# 03_-_HV_Input.net
KiCad netlist of a schematic drawn in Altium Designer
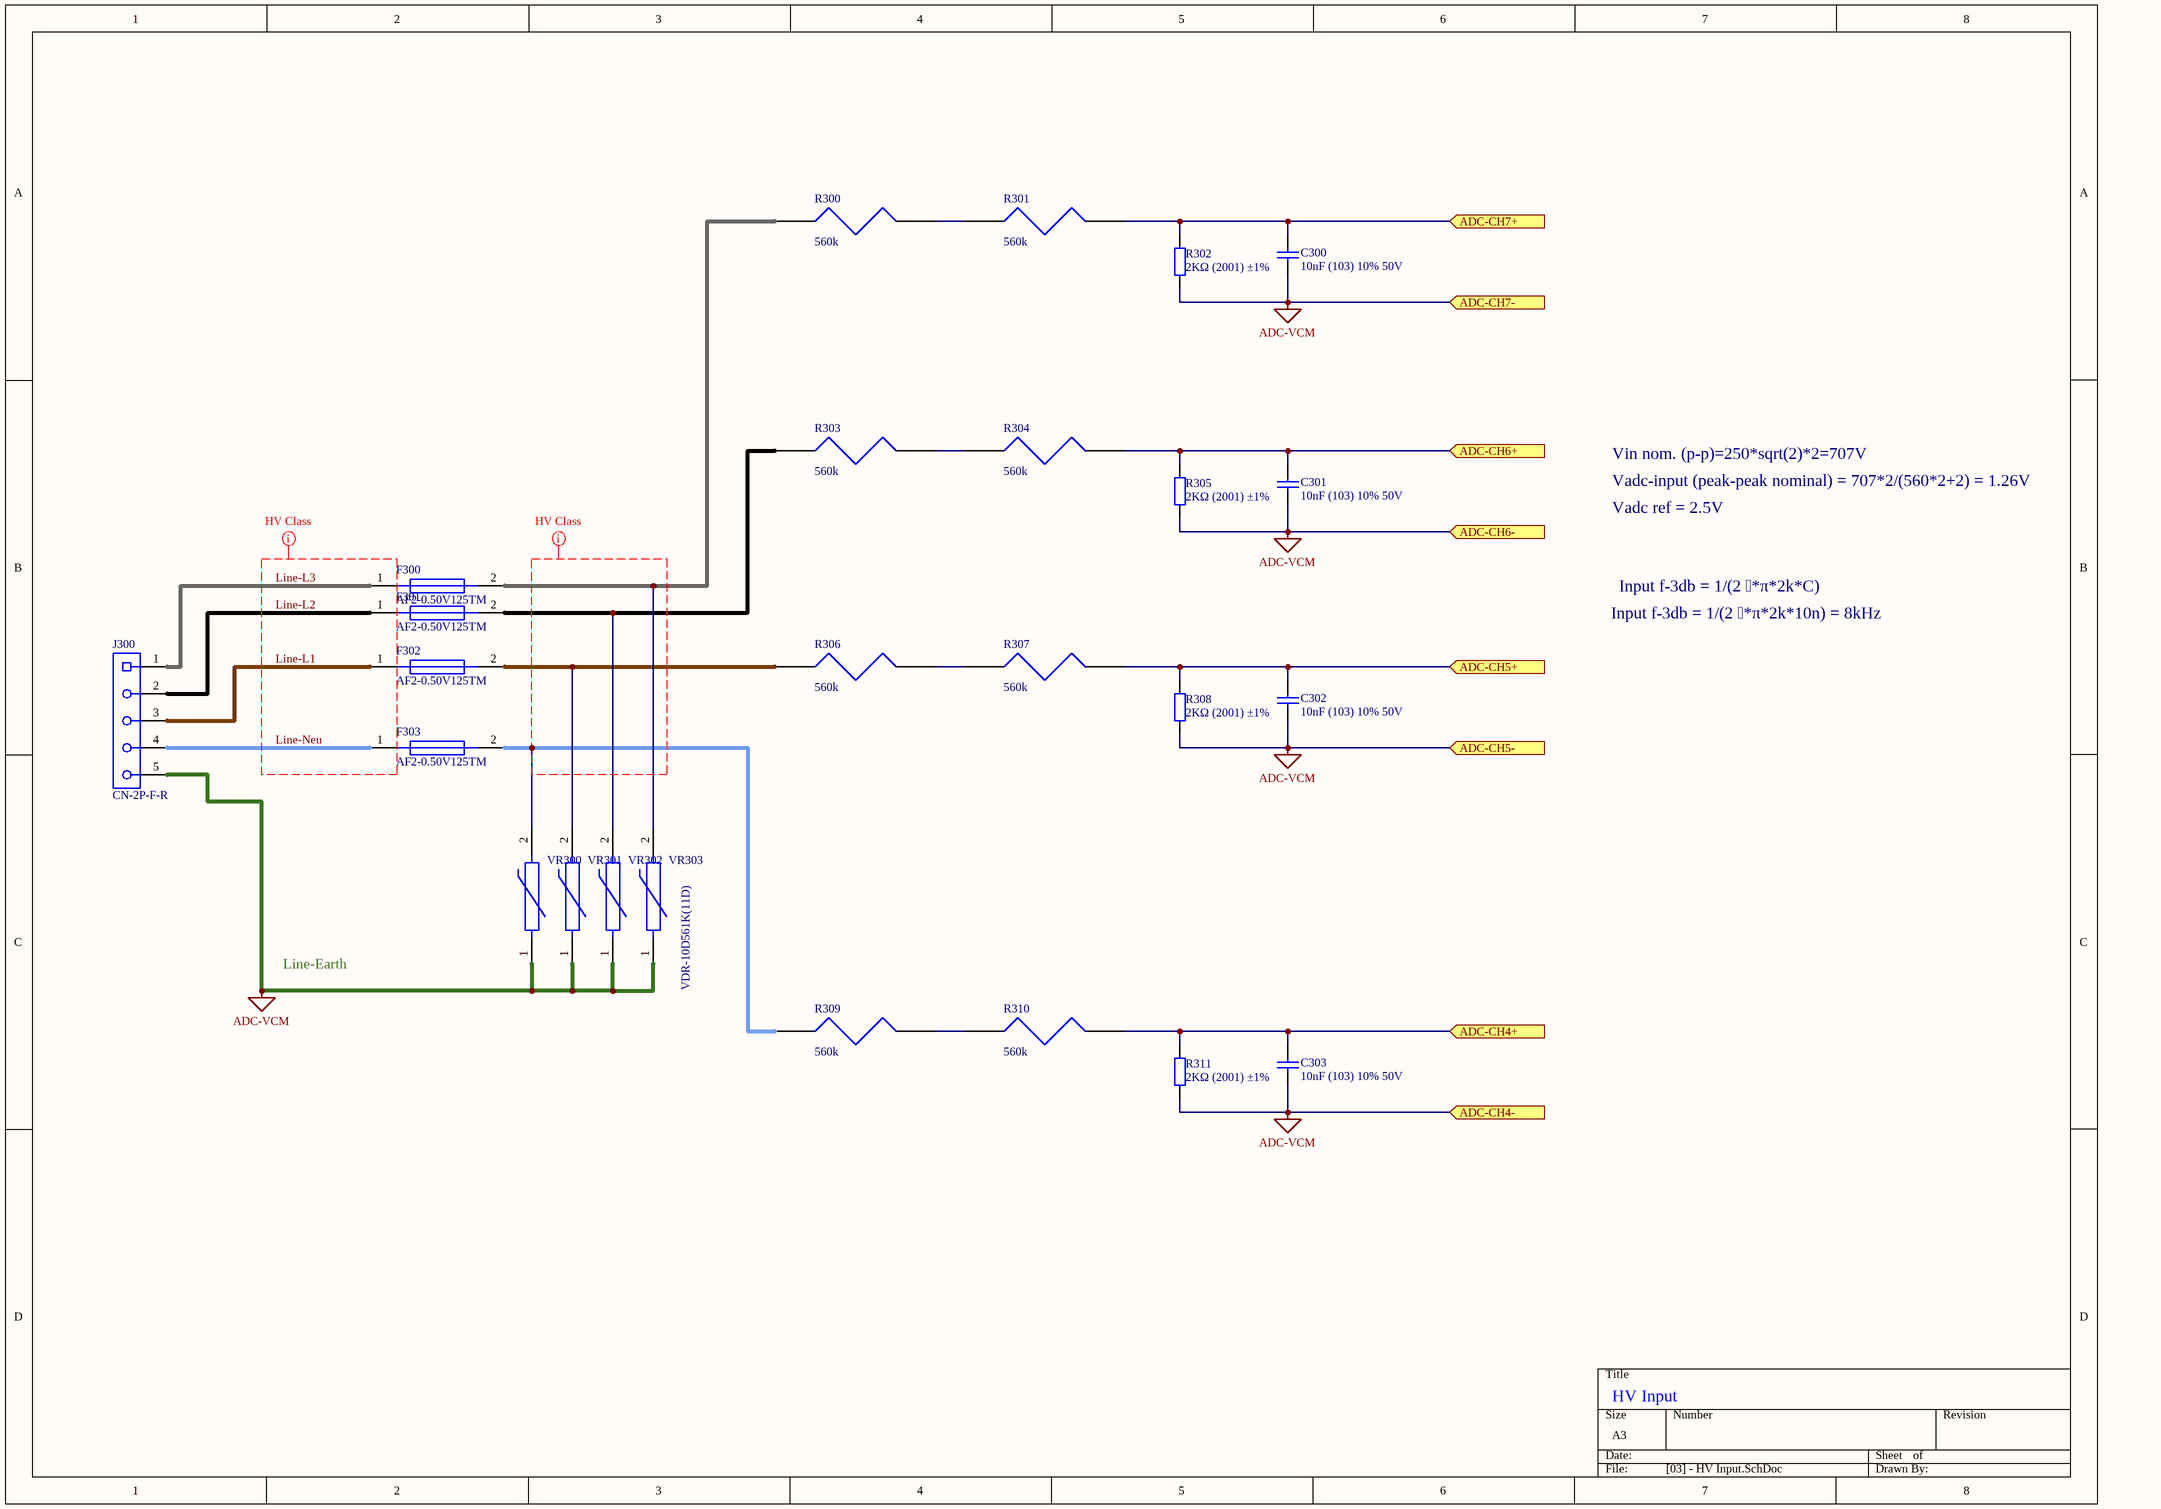
[diagram p0: [03] - HV Input.SchDoc]

(export (version "E")
  (design (tool "Eeschema 10.0.6"))
  (components
    (comp (ref "C300")
      (value "10nF (103) 10% 50V")
      (footprint "0805_C")
      (description "贴片电容")
      (libsource (lib "Cap") (part "0805 10nF (103) 10% 50V"))
    )
    (comp (ref "C301")
      (value "10nF (103) 10% 50V")
      (footprint "0805_C")
      (description "贴片电容")
      (libsource (lib "Cap") (part "0805 10nF (103) 10% 50V"))
    )
    (comp (ref "C302")
      (value "10nF (103) 10% 50V")
      (footprint "0805_C")
      (description "贴片电容")
      (libsource (lib "Cap") (part "0805 10nF (103) 10% 50V"))
    )
    (comp (ref "C303")
      (value "10nF (103) 10% 50V")
      (footprint "0805_C")
      (description "贴片电容")
      (libsource (lib "Cap") (part "0805 10nF (103) 10% 50V"))
    )
    (comp (ref "F300")
      (value "AF2-0.50V125TM")
      (footprint "2410 Fuse")
      (description "Chip Fuse Fast Blow 500mA 231mΩ 100A AC，50A DC 0.1 2410 Surface Mount Fuses RoHS")
      (libsource (lib "FPGA_PMU_lib") (part "AF2-0.50V125TM"))
    )
    (comp (ref "F301")
      (value "AF2-0.50V125TM")
      (footprint "2410 Fuse")
      (description "Chip Fuse Fast Blow 500mA 231mΩ 100A AC，50A DC 0.1 2410 Surface Mount Fuses RoHS")
      (libsource (lib "FPGA_PMU_lib") (part "AF2-0.50V125TM"))
    )
    (comp (ref "F302")
      (value "AF2-0.50V125TM")
      (footprint "2410 Fuse")
      (description "Chip Fuse Fast Blow 500mA 231mΩ 100A AC，50A DC 0.1 2410 Surface Mount Fuses RoHS")
      (libsource (lib "FPGA_PMU_lib") (part "AF2-0.50V125TM"))
    )
    (comp (ref "F303")
      (value "AF2-0.50V125TM")
      (footprint "2410 Fuse")
      (description "Chip Fuse Fast Blow 500mA 231mΩ 100A AC，50A DC 0.1 2410 Surface Mount Fuses RoHS")
      (libsource (lib "FPGA_PMU_lib") (part "AF2-0.50V125TM"))
    )
    (comp (ref "J300")
      (value "CN-2P-F-R")
      (footprint "PHOE-1729128-2_V")
      (description "5 Way - 10.16 block")
      (libsource (lib "xPMU_lib") (part "CN-2P-F-R"))
    )
    (comp (ref "R300")
      (value "560k")
      (footprint "FPGA_PMU_lib:2512_HV_RES")
      (description "HIGH VOLTAGE RESISTOR 560KOHMS ±1% 1W 2512 ROHS")
      (libsource (lib "FPGA_PMU_lib") (part "HR2512F560KE04Z"))
    )
    (comp (ref "R301")
      (value "560k")
      (footprint "FPGA_PMU_lib:2512_HV_RES")
      (description "HIGH VOLTAGE RESISTOR 560KOHMS ±1% 1W 2512 ROHS")
      (libsource (lib "FPGA_PMU_lib") (part "HR2512F560KE04Z"))
    )
    (comp (ref "R302")
      (value "2KΩ (2001) ±1%")
      (footprint "0805_R")
      (description "贴片电阻")
      (libsource (lib "RES") (part "0805 2KΩ (2001) 1%"))
    )
    (comp (ref "R303")
      (value "560k")
      (footprint "FPGA_PMU_lib:2512_HV_RES")
      (description "HIGH VOLTAGE RESISTOR 560KOHMS ±1% 1W 2512 ROHS")
      (libsource (lib "FPGA_PMU_lib") (part "HR2512F560KE04Z"))
    )
    (comp (ref "R304")
      (value "560k")
      (footprint "FPGA_PMU_lib:2512_HV_RES")
      (description "HIGH VOLTAGE RESISTOR 560KOHMS ±1% 1W 2512 ROHS")
      (libsource (lib "FPGA_PMU_lib") (part "HR2512F560KE04Z"))
    )
    (comp (ref "R305")
      (value "2KΩ (2001) ±1%")
      (footprint "0805_R")
      (description "贴片电阻")
      (libsource (lib "RES") (part "0805 2KΩ (2001) 1%"))
    )
    (comp (ref "R306")
      (value "560k")
      (footprint "FPGA_PMU_lib:2512_HV_RES")
      (description "HIGH VOLTAGE RESISTOR 560KOHMS ±1% 1W 2512 ROHS")
      (libsource (lib "FPGA_PMU_lib") (part "HR2512F560KE04Z"))
    )
    (comp (ref "R307")
      (value "560k")
      (footprint "FPGA_PMU_lib:2512_HV_RES")
      (description "HIGH VOLTAGE RESISTOR 560KOHMS ±1% 1W 2512 ROHS")
      (libsource (lib "FPGA_PMU_lib") (part "HR2512F560KE04Z"))
    )
    (comp (ref "R308")
      (value "2KΩ (2001) ±1%")
      (footprint "0805_R")
      (description "贴片电阻")
      (libsource (lib "RES") (part "0805 2KΩ (2001) 1%"))
    )
    (comp (ref "R309")
      (value "560k")
      (footprint "FPGA_PMU_lib:2512_HV_RES")
      (description "HIGH VOLTAGE RESISTOR 560KOHMS ±1% 1W 2512 ROHS")
      (libsource (lib "FPGA_PMU_lib") (part "HR2512F560KE04Z"))
    )
    (comp (ref "R310")
      (value "560k")
      (footprint "FPGA_PMU_lib:2512_HV_RES")
      (description "HIGH VOLTAGE RESISTOR 560KOHMS ±1% 1W 2512 ROHS")
      (libsource (lib "FPGA_PMU_lib") (part "HR2512F560KE04Z"))
    )
    (comp (ref "R311")
      (value "2KΩ (2001) ±1%")
      (footprint "0805_R")
      (description "贴片电阻")
      (libsource (lib "RES") (part "0805 2KΩ (2001) 1%"))
    )
    (comp (ref "VR300")
      (value "VDR-10D561K(11D)")
      (footprint "VDR-10D561K(11D)")
      (description "460V 920V 2.5KA 560V Through Hole Varistors RoHS")
      (libsource (lib "FPGA_PMU_lib") (part "VDR-10D561K(11D)"))
    )
    (comp (ref "VR301")
      (value "VDR-10D561K(11D)")
      (footprint "VDR-10D561K(11D)")
      (description "460V 920V 2.5KA 560V Through Hole Varistors RoHS")
      (libsource (lib "FPGA_PMU_lib") (part "VDR-10D561K(11D)"))
    )
    (comp (ref "VR302")
      (value "VDR-10D561K(11D)")
      (footprint "VDR-10D561K(11D)")
      (description "460V 920V 2.5KA 560V Through Hole Varistors RoHS")
      (libsource (lib "FPGA_PMU_lib") (part "VDR-10D561K(11D)"))
    )
    (comp (ref "VR303")
      (value "VDR-10D561K(11D)")
      (footprint "VDR-10D561K(11D)")
      (description "460V 920V 2.5KA 560V Through Hole Varistors RoHS")
      (libsource (lib "FPGA_PMU_lib") (part "VDR-10D561K(11D)"))
    )
  )
  (nets
    (net (code "1") (name "/ADC-CH4+") (class "Default")
      (node (ref "C303") (pin "2") (pinfunction "2_2") (pintype "passive"))
      (node (ref "R310") (pin "2") (pinfunction "2_2") (pintype "passive"))
      (node (ref "R311") (pin "2") (pinfunction "2_2") (pintype "passive"))
    )
    (net (code "2") (name "/ADC-CH5+") (class "Default")
      (node (ref "C302") (pin "2") (pinfunction "2_2") (pintype "passive"))
      (node (ref "R307") (pin "2") (pinfunction "2_2") (pintype "passive"))
      (node (ref "R308") (pin "2") (pinfunction "2_2") (pintype "passive"))
    )
    (net (code "3") (name "/ADC-CH6+") (class "Default")
      (node (ref "C301") (pin "2") (pinfunction "2_2") (pintype "passive"))
      (node (ref "R304") (pin "2") (pinfunction "2_2") (pintype "passive"))
      (node (ref "R305") (pin "2") (pinfunction "2_2") (pintype "passive"))
    )
    (net (code "4") (name "/ADC-CH7+") (class "Default")
      (node (ref "C300") (pin "2") (pinfunction "2_2") (pintype "passive"))
      (node (ref "R301") (pin "2") (pinfunction "2_2") (pintype "passive"))
      (node (ref "R302") (pin "2") (pinfunction "2_2") (pintype "passive"))
    )
    (net (code "5") (name "/Line-L1") (class "Default")
      (node (ref "F302") (pin "1") (pinfunction "1_1") (pintype "passive"))
      (node (ref "J300") (pin "3") (pinfunction "3_3") (pintype "passive"))
    )
    (net (code "6") (name "/Line-L2") (class "Default")
      (node (ref "F301") (pin "1") (pinfunction "1_1") (pintype "passive"))
      (node (ref "J300") (pin "2") (pinfunction "2_2") (pintype "passive"))
    )
    (net (code "7") (name "/Line-L3") (class "Default")
      (node (ref "F300") (pin "1") (pinfunction "1_1") (pintype "passive"))
      (node (ref "J300") (pin "1") (pinfunction "1_1") (pintype "passive"))
    )
    (net (code "8") (name "/Line-Neu") (class "Default")
      (node (ref "F303") (pin "1") (pinfunction "1_1") (pintype "passive"))
      (node (ref "J300") (pin "4") (pinfunction "4_4") (pintype "passive"))
    )
    (net (code "9") (name "ADC-VCM") (class "Default")
      (node (ref "C300") (pin "1") (pinfunction "1_1") (pintype "passive"))
      (node (ref "C301") (pin "1") (pinfunction "1_1") (pintype "passive"))
      (node (ref "C302") (pin "1") (pinfunction "1_1") (pintype "passive"))
      (node (ref "C303") (pin "1") (pinfunction "1_1") (pintype "passive"))
      (node (ref "J300") (pin "5") (pinfunction "5_5") (pintype "passive"))
      (node (ref "R302") (pin "1") (pinfunction "1_1") (pintype "passive"))
      (node (ref "R305") (pin "1") (pinfunction "1_1") (pintype "passive"))
      (node (ref "R308") (pin "1") (pinfunction "1_1") (pintype "passive"))
      (node (ref "R311") (pin "1") (pinfunction "1_1") (pintype "passive"))
      (node (ref "VR300") (pin "1") (pinfunction "1_1") (pintype "passive"))
      (node (ref "VR301") (pin "1") (pinfunction "1_1") (pintype "passive"))
      (node (ref "VR302") (pin "1") (pinfunction "1_1") (pintype "passive"))
      (node (ref "VR303") (pin "1") (pinfunction "1_1") (pintype "passive"))
    )
    (net (code "10") (name "Net-(F300-Pad2)") (class "Default")
      (node (ref "F300") (pin "2") (pinfunction "2_2") (pintype "passive"))
      (node (ref "R300") (pin "1") (pinfunction "1_1") (pintype "passive"))
      (node (ref "VR303") (pin "2") (pinfunction "2_2") (pintype "passive"))
    )
    (net (code "11") (name "Net-(F301-Pad2)") (class "Default")
      (node (ref "F301") (pin "2") (pinfunction "2_2") (pintype "passive"))
      (node (ref "R303") (pin "1") (pinfunction "1_1") (pintype "passive"))
      (node (ref "VR302") (pin "2") (pinfunction "2_2") (pintype "passive"))
    )
    (net (code "12") (name "Net-(F302-Pad2)") (class "Default")
      (node (ref "F302") (pin "2") (pinfunction "2_2") (pintype "passive"))
      (node (ref "R306") (pin "1") (pinfunction "1_1") (pintype "passive"))
      (node (ref "VR301") (pin "2") (pinfunction "2_2") (pintype "passive"))
    )
    (net (code "13") (name "Net-(F303-Pad2)") (class "Default")
      (node (ref "F303") (pin "2") (pinfunction "2_2") (pintype "passive"))
      (node (ref "R309") (pin "1") (pinfunction "1_1") (pintype "passive"))
      (node (ref "VR300") (pin "2") (pinfunction "2_2") (pintype "passive"))
    )
    (net (code "14") (name "Net-(R300-Pad2)") (class "Default")
      (node (ref "R300") (pin "2") (pinfunction "2_2") (pintype "passive"))
      (node (ref "R301") (pin "1") (pinfunction "1_1") (pintype "passive"))
    )
    (net (code "15") (name "Net-(R303-Pad2)") (class "Default")
      (node (ref "R303") (pin "2") (pinfunction "2_2") (pintype "passive"))
      (node (ref "R304") (pin "1") (pinfunction "1_1") (pintype "passive"))
    )
    (net (code "16") (name "Net-(R306-Pad2)") (class "Default")
      (node (ref "R306") (pin "2") (pinfunction "2_2") (pintype "passive"))
      (node (ref "R307") (pin "1") (pinfunction "1_1") (pintype "passive"))
    )
    (net (code "17") (name "Net-(R309-Pad2)") (class "Default")
      (node (ref "R309") (pin "2") (pinfunction "2_2") (pintype "passive"))
      (node (ref "R310") (pin "1") (pinfunction "1_1") (pintype "passive"))
    )
  )
)
